# INMP441.net
KiCad netlist of a schematic drawn in Altium Designer
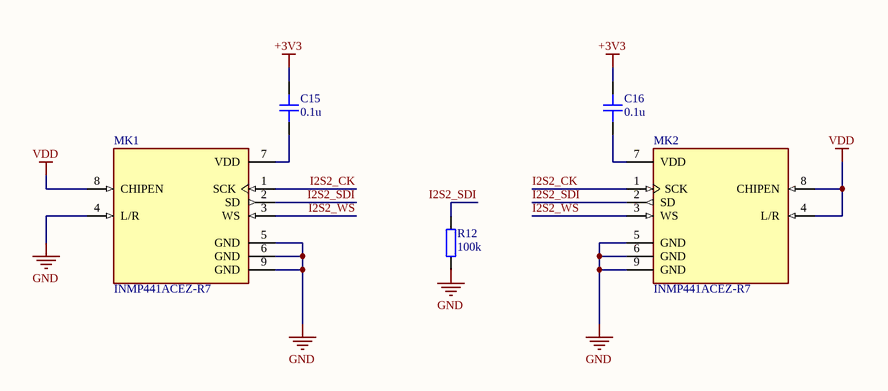
[diagram p0: INMP441.SchDoc]

(export (version "E")
  (design (tool "Eeschema 10.0.6"))
  (components
    (comp (ref "C15")
      (value "0.1u")
      (footprint "CAP_0402")
      (description "Capacitor SMD 0402")
      (libsource (lib "Schematic-Lib-PhilsLab") (part "CAP_0402"))
    )
    (comp (ref "C16")
      (value "0.1u")
      (footprint "CAP_0402")
      (description "Capacitor SMD 0402")
      (libsource (lib "Schematic-Lib-PhilsLab") (part "CAP_0402"))
    )
    (comp (ref "MK1")
      (value "INMP441ACEZ-R7")
      (footprint "MIC_INMP441ACEZ-R7")
      (fields (field (name "MF") "TDK InvenSense"))
      (libsource (lib "INMP441ACEZ-R7") (part "INMP441ACEZ-R7"))
    )
    (comp (ref "MK2")
      (value "INMP441ACEZ-R7")
      (footprint "MIC_INMP441ACEZ-R7")
      (fields (field (name "MF") "TDK InvenSense"))
      (libsource (lib "") (part "INMP441ACEZ-R7_1"))
    )
    (comp (ref "R12")
      (value "100k")
      (footprint "RES_0402")
      (description "Resistor SMD 0402")
      (libsource (lib "Schematic-Lib-PhilsLab") (part "RES_0402"))
    )
  )
  (nets
    (net (code "1") (name "+3V3") (class "Default")
      (node (ref "C15") (pin "2") (pinfunction "2_2") (pintype "passive"))
      (node (ref "C16") (pin "2") (pinfunction "2_2") (pintype "passive"))
    )
    (net (code "2") (name "/I2S2_CK") (class "Default")
      (node (ref "MK1") (pin "1") (pinfunction "SCK_1") (pintype "input"))
      (node (ref "MK2") (pin "1") (pinfunction "SCK_1") (pintype "input"))
    )
    (net (code "3") (name "/I2S2_SDI") (class "Default")
      (node (ref "MK1") (pin "2") (pinfunction "SD_2") (pintype "output"))
      (node (ref "MK2") (pin "2") (pinfunction "SD_2") (pintype "output"))
      (node (ref "R12") (pin "2") (pinfunction "2_2") (pintype "passive"))
    )
    (net (code "4") (name "/I2S2_WS") (class "Default")
      (node (ref "MK1") (pin "3") (pinfunction "WS_3") (pintype "input"))
      (node (ref "MK2") (pin "3") (pinfunction "WS_3") (pintype "input"))
    )
    (net (code "5") (name "GND") (class "Default")
      (node (ref "MK1") (pin "4") (pinfunction "L/R_4") (pintype "input"))
      (node (ref "MK1") (pin "5") (pinfunction "GND_5") (pintype "power_in"))
      (node (ref "MK1") (pin "6") (pinfunction "GND_6") (pintype "power_in"))
      (node (ref "MK1") (pin "9") (pinfunction "GND_9") (pintype "power_in"))
      (node (ref "MK2") (pin "5") (pinfunction "GND_5") (pintype "power_in"))
      (node (ref "MK2") (pin "6") (pinfunction "GND_6") (pintype "power_in"))
      (node (ref "MK2") (pin "9") (pinfunction "GND_9") (pintype "power_in"))
      (node (ref "R12") (pin "1") (pinfunction "1_1") (pintype "passive"))
    )
    (net (code "6") (name "Net-(MK1-VDD)") (class "Default")
      (node (ref "C15") (pin "1") (pinfunction "1_1") (pintype "passive"))
      (node (ref "MK1") (pin "7") (pinfunction "VDD_7") (pintype "power_in"))
    )
    (net (code "7") (name "Net-(MK2-VDD)") (class "Default")
      (node (ref "C16") (pin "1") (pinfunction "1_1") (pintype "passive"))
      (node (ref "MK2") (pin "7") (pinfunction "VDD_7") (pintype "power_in"))
    )
    (net (code "8") (name "VDD") (class "Default")
      (node (ref "MK1") (pin "8") (pinfunction "CHIPEN_8") (pintype "input"))
      (node (ref "MK2") (pin "4") (pinfunction "L/R_4") (pintype "input"))
      (node (ref "MK2") (pin "8") (pinfunction "CHIPEN_8") (pintype "input"))
    )
  )
)
